# AHRS_board.net
KiCad netlist of a schematic drawn in Altium Designer
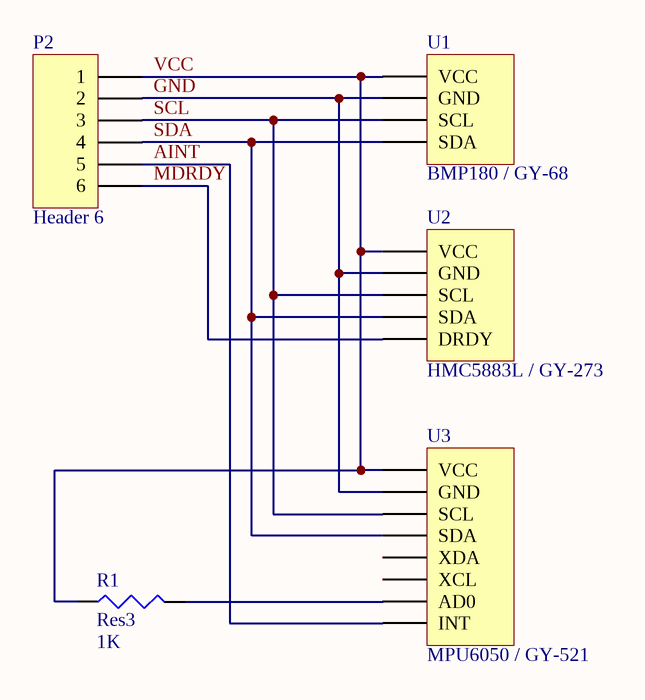
[diagram p0: AHRS_board.SchDoc]

(export (version "E")
  (design (tool "Eeschema 10.0.6"))
  (components
    (comp (ref "P2")
      (value "Header 6")
      (footprint "HDR1X6")
      (description "Header, 6-Pin")
      (fields (field (name "PUBLISHER") "Altium Limited"))
      (libsource (lib "Miscellaneous Connectors") (part "Header 6"))
    )
    (comp (ref "R1")
      (value "Res3")
      (footprint "J1-0603")
      (description "Resistor")
      (fields (field (name "ALTIUM_VALUE") "1K") (field (name "PUBLISHER") "Altium Limited"))
      (libsource (lib "Miscellaneous Devices") (part "Res3"))
    )
    (comp (ref "U1")
      (value "BMP180 / GY-68")
      (footprint "BMP180")
      (libsource (lib "MyLib") (part "BMP180 / GY-68"))
    )
    (comp (ref "U2")
      (value "HMC5883L / GY-273")
      (footprint "HMC5883L")
      (libsource (lib "MyLib") (part "HMC5883L / GY-273"))
    )
    (comp (ref "U3")
      (value "MPU6050 / GY-521")
      (footprint "MPU6050")
      (libsource (lib "MyLib") (part "MPU6050 / GY-521"))
    )
  )
  (nets
    (net (code "1") (name "/AINT") (class "Default")
      (node (ref "P2") (pin "5") (pinfunction "5_5") (pintype "passive"))
      (node (ref "U3") (pin "8") (pinfunction "INT_8") (pintype "passive"))
    )
    (net (code "2") (name "/GND") (class "Default")
      (node (ref "P2") (pin "2") (pinfunction "2_2") (pintype "passive"))
      (node (ref "U1") (pin "2") (pinfunction "GND_2") (pintype "passive"))
      (node (ref "U2") (pin "2") (pinfunction "GND_2") (pintype "passive"))
      (node (ref "U3") (pin "2") (pinfunction "GND_2") (pintype "passive"))
    )
    (net (code "3") (name "/MDRDY") (class "Default")
      (node (ref "P2") (pin "6") (pinfunction "6_6") (pintype "passive"))
      (node (ref "U2") (pin "5") (pinfunction "DRDY_5") (pintype "passive"))
    )
    (net (code "4") (name "/SCL") (class "Default")
      (node (ref "P2") (pin "3") (pinfunction "3_3") (pintype "passive"))
      (node (ref "U1") (pin "3") (pinfunction "SCL_3") (pintype "passive"))
      (node (ref "U2") (pin "3") (pinfunction "SCL_3") (pintype "passive"))
      (node (ref "U3") (pin "3") (pinfunction "SCL_3") (pintype "passive"))
    )
    (net (code "5") (name "/SDA") (class "Default")
      (node (ref "P2") (pin "4") (pinfunction "4_4") (pintype "passive"))
      (node (ref "U1") (pin "4") (pinfunction "SDA_4") (pintype "passive"))
      (node (ref "U2") (pin "4") (pinfunction "SDA_4") (pintype "passive"))
      (node (ref "U3") (pin "4") (pinfunction "SDA_4") (pintype "passive"))
    )
    (net (code "6") (name "/VCC") (class "Default")
      (node (ref "P2") (pin "1") (pinfunction "1_1") (pintype "passive"))
      (node (ref "R1") (pin "1") (pinfunction "1_1") (pintype "passive"))
      (node (ref "U1") (pin "1") (pinfunction "VCC_1") (pintype "passive"))
      (node (ref "U2") (pin "1") (pinfunction "VCC_1") (pintype "passive"))
      (node (ref "U3") (pin "1") (pinfunction "VCC_1") (pintype "passive"))
    )
    (net (code "7") (name "Net-(U3-AD0)") (class "Default")
      (node (ref "R1") (pin "2") (pinfunction "2_2") (pintype "passive"))
      (node (ref "U3") (pin "7") (pinfunction "AD0_7") (pintype "passive"))
    )
    (net (code "8") (name "unconnected-(U3-XCL-Pad6)") (class "Default")
      (node (ref "U3") (pin "6") (pinfunction "XCL_6") (pintype "passive"))
    )
    (net (code "9") (name "unconnected-(U3-XDA-Pad5)") (class "Default")
      (node (ref "U3") (pin "5") (pinfunction "XDA_5") (pintype "passive"))
    )
  )
)
